# SCH_Business-Card.net
KiCad netlist of a schematic drawn in EasyEDA
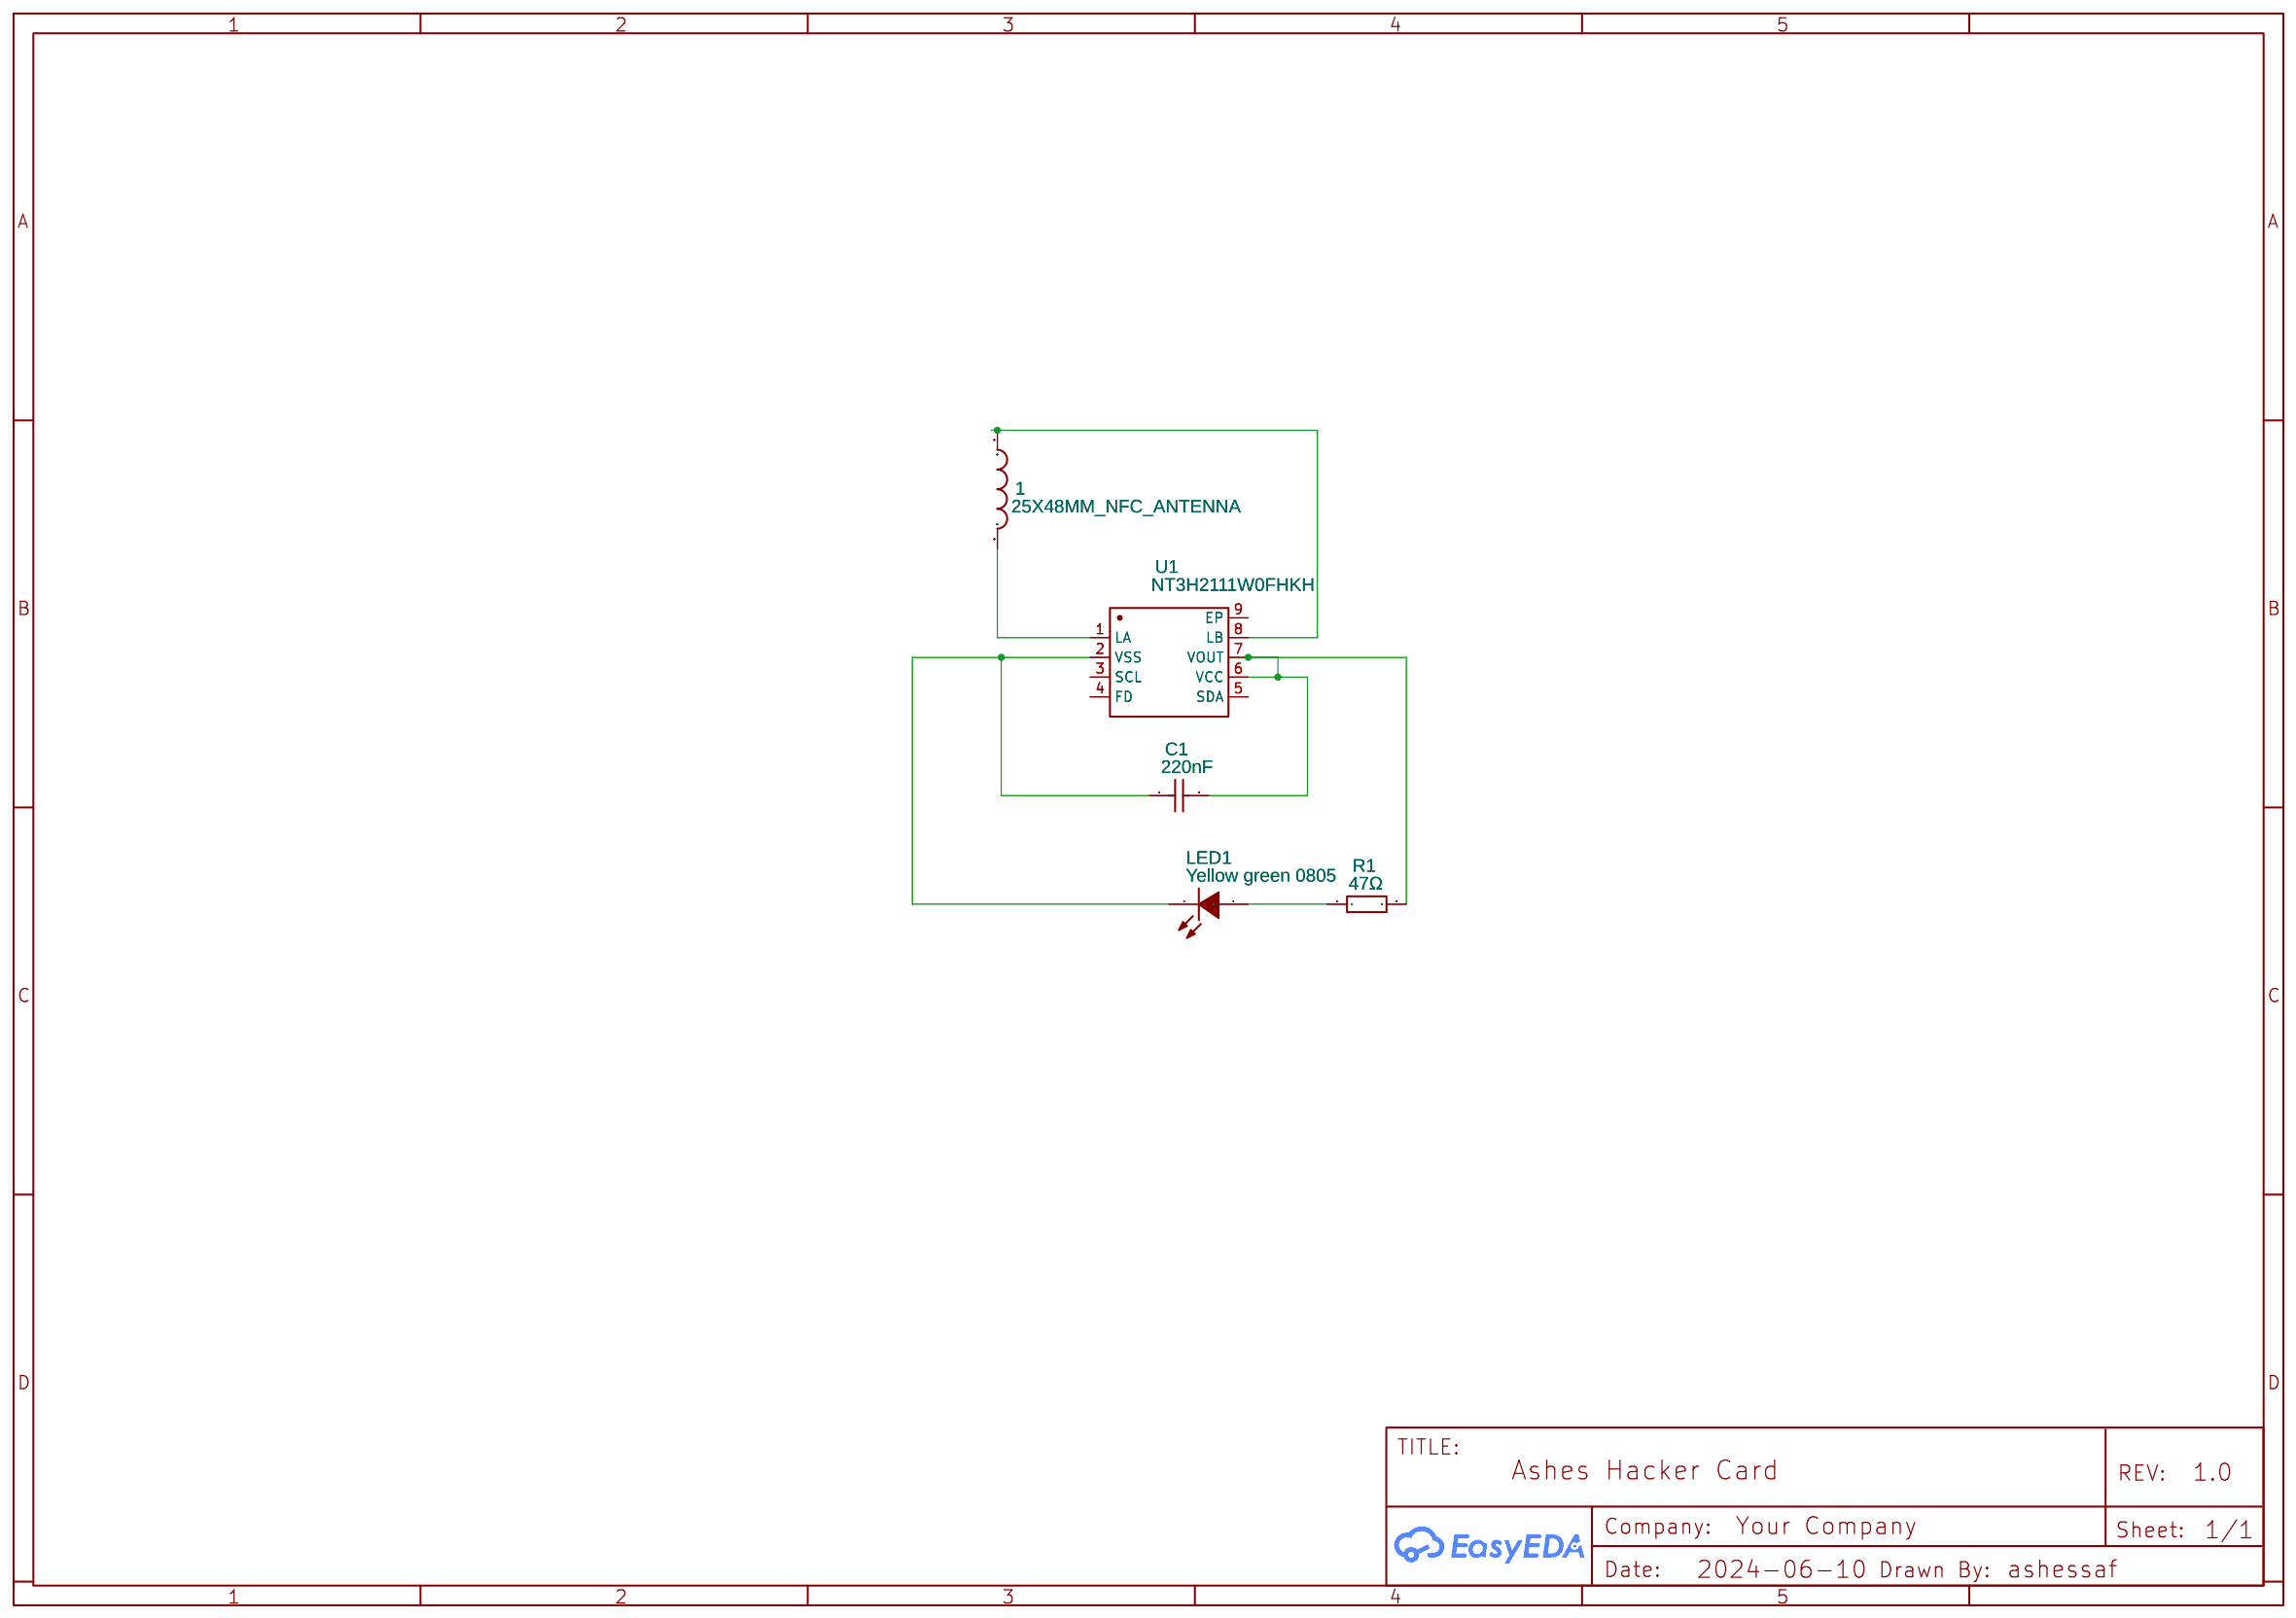
[diagram p0: schematic sheet]

(export (version "E")
  (design (tool "Eeschema 10.0.6"))
  (components
    (comp (ref "1") (value "25X48MM_NFC_ANTENNA") (libsource (lib "") (part "25X48MM_NFC_ANTENNA")))
    (comp (ref "C1")
      (value "220nF")
      (fields
        (field (name "Manufacturer Part") "CL10B224KA8NNNC")
        (field (name "Manufacturer") "SAMSUNG(三星)")
      )
      (libsource (lib "") (part "CL10B224KA8NNNC"))
    )
    (comp (ref "LED1")
      (value "Yellow green 0805")
      (fields (field (name "Manufacturer Part") "KT-0805YG") (field (name "Manufacturer") "KENTO"))
      (libsource (lib "") (part "Yellow green 0805"))
    )
    (comp (ref "R1")
      (value "47Ω")
      (fields
        (field (name "Manufacturer Part") "0603WAF470JT5E")
        (field (name "Manufacturer") "UNI-ROYAL(厚声)")
      )
      (libsource (lib "") (part "0603WAF470JT5E"))
    )
    (comp (ref "U1")
      (value "NT3H2111W0FHKH")
      (fields (field (name "Manufacturer") "NXP(恩智浦)"))
      (libsource (lib "") (part "NT3H2111W0FHKH"))
    )
  )
  (nets
    (net (code "1") (name "Net-(LED1-A)") (class "Default")
      (node (ref "LED1") (pin "1") (pinfunction "A_1") (pintype "unspecified"))
      (node (ref "R1") (pin "1") (pinfunction "1_1") (pintype "input"))
    )
    (net (code "2") (name "Net-(LED1-K)") (class "Default")
      (node (ref "C1") (pin "1") (pinfunction "1_1") (pintype "input"))
      (node (ref "LED1") (pin "2") (pinfunction "K_2") (pintype "unspecified"))
      (node (ref "U1") (pin "2") (pinfunction "VSS_2") (pintype "unspecified"))
    )
    (net (code "3") (name "Net-(U1-LA)") (class "Default")
      (node (ref "1") (pin "P$2") (pinfunction "P$2_P$2") (pintype "bidirectional"))
      (node (ref "U1") (pin "1") (pinfunction "LA_1") (pintype "unspecified"))
    )
    (net (code "4") (name "Net-(U1-LB)") (class "Default")
      (node (ref "1") (pin "P$1") (pinfunction "P$1_P$1") (pintype "bidirectional"))
      (node (ref "U1") (pin "8") (pinfunction "LB_8") (pintype "unspecified"))
    )
    (net (code "5") (name "Net-(U1-VCC)") (class "Default")
      (node (ref "C1") (pin "2") (pinfunction "2_2") (pintype "input"))
      (node (ref "R1") (pin "2") (pinfunction "2_2") (pintype "input"))
      (node (ref "U1") (pin "6") (pinfunction "VCC_6") (pintype "unspecified"))
      (node (ref "U1") (pin "7") (pinfunction "VOUT_7") (pintype "unspecified"))
    )
    (net (code "6") (name "unconnected-(U1-EP-Pad9)") (class "Default")
      (node (ref "U1") (pin "9") (pinfunction "EP_9") (pintype "unspecified"))
    )
    (net (code "7") (name "unconnected-(U1-FD-Pad4)") (class "Default")
      (node (ref "U1") (pin "4") (pinfunction "FD_4") (pintype "unspecified"))
    )
    (net (code "8") (name "unconnected-(U1-SCL-Pad3)") (class "Default")
      (node (ref "U1") (pin "3") (pinfunction "SCL_3") (pintype "unspecified"))
    )
    (net (code "9") (name "unconnected-(U1-SDA-Pad5)") (class "Default")
      (node (ref "U1") (pin "5") (pinfunction "SDA_5") (pintype "unspecified"))
    )
  )
)
